# PWM_CON_Outputs.net
KiCad netlist of a schematic drawn in Altium Designer
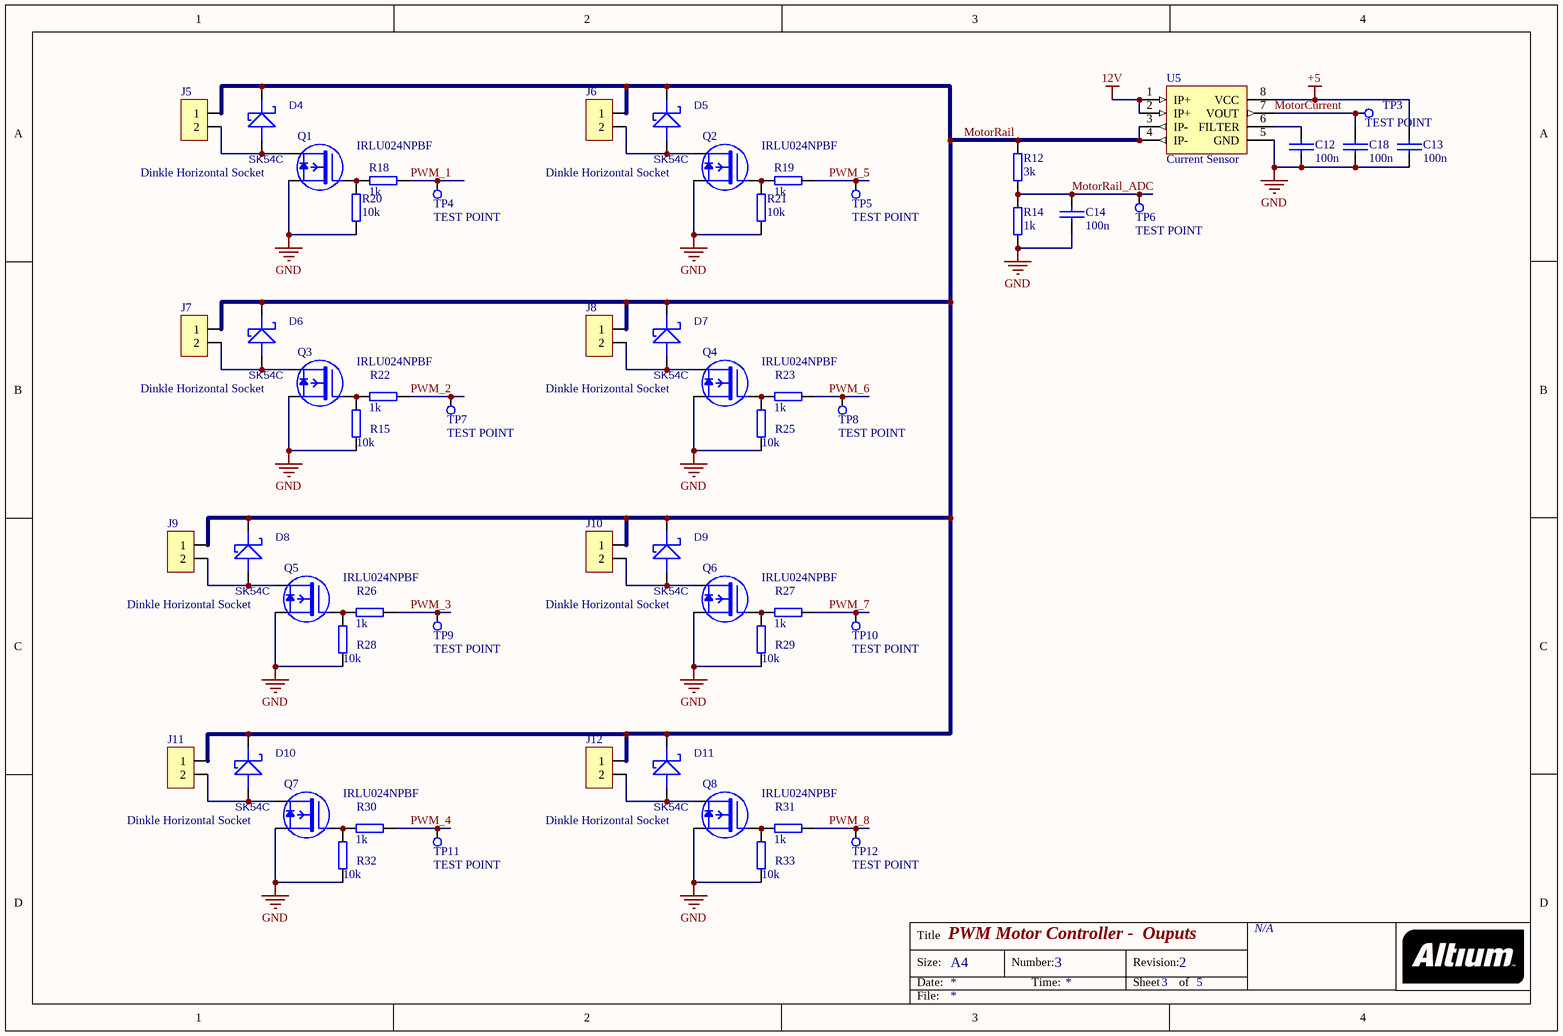
[diagram p0: PWM_CON_Outputs.SchDoc]

(export (version "E")
  (design (tool "Eeschema 10.0.6"))
  (components
    (comp (ref "C12")
      (value "100n")
      (footprint "0603")
      (fields (field (name "PARTNO") "R8835"))
      (libsource (lib "*") (part "CAP"))
    )
    (comp (ref "C13")
      (value "100n")
      (footprint "0603")
      (fields (field (name "PARTNO") "R8835"))
      (libsource (lib "*") (part "CAP"))
    )
    (comp (ref "C14")
      (value "100n")
      (footprint "0603")
      (fields (field (name "PARTNO") "R8835"))
      (libsource (lib "*") (part "CAP"))
    )
    (comp (ref "C18")
      (value "100n")
      (footprint "0603")
      (fields (field (name "PARTNO") "R8835"))
      (libsource (lib "*") (part "CAP"))
    )
    (comp (ref "D4")
      (value "SK54C")
      (footprint "SMC")
      (fields (field (name "PARTNO") "1299291"))
      (libsource (lib "DEVICE") (part "DIODE SCHOTTKY"))
    )
    (comp (ref "D5")
      (value "SK54C")
      (footprint "SMC")
      (fields (field (name "PARTNO") "1299291"))
      (libsource (lib "DEVICE") (part "DIODE SCHOTTKY"))
    )
    (comp (ref "D6")
      (value "SK54C")
      (footprint "SMC")
      (fields (field (name "PARTNO") "1299291"))
      (libsource (lib "DEVICE") (part "DIODE SCHOTTKY"))
    )
    (comp (ref "D7")
      (value "SK54C")
      (footprint "SMC")
      (fields (field (name "PARTNO") "1299291"))
      (libsource (lib "DEVICE") (part "DIODE SCHOTTKY"))
    )
    (comp (ref "D8")
      (value "SK54C")
      (footprint "SMC")
      (fields (field (name "PARTNO") "1299291"))
      (libsource (lib "DEVICE") (part "DIODE SCHOTTKY"))
    )
    (comp (ref "D9")
      (value "SK54C")
      (footprint "SMC")
      (fields (field (name "PARTNO") "1299291"))
      (libsource (lib "DEVICE") (part "DIODE SCHOTTKY"))
    )
    (comp (ref "D10")
      (value "SK54C")
      (footprint "SMC")
      (fields (field (name "PARTNO") "1299291"))
      (libsource (lib "DEVICE") (part "DIODE SCHOTTKY"))
    )
    (comp (ref "D11")
      (value "SK54C")
      (footprint "SMC")
      (fields (field (name "PARTNO") "1299291"))
      (libsource (lib "DEVICE") (part "DIODE SCHOTTKY"))
    )
    (comp (ref "J5")
      (value "Dinkle Horizontal Socket")
      (footprint "WEID2R")
      (fields (field (name "PARTNO") "P2552"))
      (libsource (lib "DEVICE") (part "CON2"))
    )
    (comp (ref "J6")
      (value "Dinkle Horizontal Socket")
      (footprint "WEID2R")
      (fields (field (name "PARTNO") "P2552"))
      (libsource (lib "DEVICE") (part "CON2"))
    )
    (comp (ref "J7")
      (value "Dinkle Horizontal Socket")
      (footprint "WEID2R")
      (fields (field (name "PARTNO") "P2552"))
      (libsource (lib "DEVICE") (part "CON2"))
    )
    (comp (ref "J8")
      (value "Dinkle Horizontal Socket")
      (footprint "WEID2R")
      (fields (field (name "PARTNO") "P2552"))
      (libsource (lib "DEVICE") (part "CON2"))
    )
    (comp (ref "J9")
      (value "Dinkle Horizontal Socket")
      (footprint "WEID2R")
      (fields (field (name "PARTNO") "P2552"))
      (libsource (lib "DEVICE") (part "CON2"))
    )
    (comp (ref "J10")
      (value "Dinkle Horizontal Socket")
      (footprint "WEID2R")
      (fields (field (name "PARTNO") "P2552"))
      (libsource (lib "DEVICE") (part "CON2"))
    )
    (comp (ref "J11")
      (value "Dinkle Horizontal Socket")
      (footprint "WEID2R")
      (fields (field (name "PARTNO") "P2552"))
      (libsource (lib "DEVICE") (part "CON2"))
    )
    (comp (ref "J12")
      (value "Dinkle Horizontal Socket")
      (footprint "WEID2R")
      (fields (field (name "PARTNO") "P2552"))
      (libsource (lib "DEVICE") (part "CON2"))
    )
    (comp (ref "Q1")
      (value "IRLU024NPBF")
      (footprint "TO-251")
      (description "N Channel MOSFET")
      (fields (field (name "PARTNO") "8651329"))
      (libsource (lib "DEVICE") (part "MOSFET-N1DSML"))
    )
    (comp (ref "Q2")
      (value "IRLU024NPBF")
      (footprint "TO-251")
      (description "N Channel MOSFET")
      (fields (field (name "PARTNO") "8651329"))
      (libsource (lib "DEVICE") (part "MOSFET-N1DSML"))
    )
    (comp (ref "Q3")
      (value "IRLU024NPBF")
      (footprint "TO-251")
      (description "N Channel MOSFET")
      (fields (field (name "PARTNO") "8651329"))
      (libsource (lib "DEVICE") (part "MOSFET-N1DSML"))
    )
    (comp (ref "Q4")
      (value "IRLU024NPBF")
      (footprint "TO-251")
      (description "N Channel MOSFET")
      (fields (field (name "PARTNO") "8651329"))
      (libsource (lib "DEVICE") (part "MOSFET-N1DSML"))
    )
    (comp (ref "Q5")
      (value "IRLU024NPBF")
      (footprint "TO-251")
      (description "N Channel MOSFET")
      (fields (field (name "PARTNO") "8651329"))
      (libsource (lib "DEVICE") (part "MOSFET-N1DSML"))
    )
    (comp (ref "Q6")
      (value "IRLU024NPBF")
      (footprint "TO-251")
      (description "N Channel MOSFET")
      (fields (field (name "PARTNO") "8651329"))
      (libsource (lib "DEVICE") (part "MOSFET-N1DSML"))
    )
    (comp (ref "Q7")
      (value "IRLU024NPBF")
      (footprint "TO-251")
      (description "N Channel MOSFET")
      (fields (field (name "PARTNO") "8651329"))
      (libsource (lib "DEVICE") (part "MOSFET-N1DSML"))
    )
    (comp (ref "Q8")
      (value "IRLU024NPBF")
      (footprint "TO-251")
      (description "N Channel MOSFET")
      (fields (field (name "PARTNO") "8651329"))
      (libsource (lib "DEVICE") (part "MOSFET-N1DSML"))
    )
    (comp (ref "R12")
      (value "3k")
      (footprint "0603")
      (description "1% Resistor")
      (fields (field (name "PARTNO") "R1629"))
      (libsource (lib "DEVICE") (part "RES8"))
    )
    (comp (ref "R14")
      (value "1k")
      (footprint "0603")
      (description "1% Resistor")
      (fields (field (name "PARTNO") "R1596"))
      (libsource (lib "") (part "RES8_1"))
    )
    (comp (ref "R15")
      (value "10k")
      (footprint "0603")
      (description "1% Resistor")
      (fields (field (name "PARTNO") "R1668"))
      (libsource (lib "DEVICE") (part "RES8"))
    )
    (comp (ref "R18")
      (value "1k")
      (footprint "0603")
      (description "1% Resistor")
      (fields (field (name "PARTNO") "R1596"))
      (libsource (lib "DEVICE") (part "RES8"))
    )
    (comp (ref "R19")
      (value "1k")
      (footprint "0603")
      (description "1% Resistor")
      (fields (field (name "PARTNO") "R1596"))
      (libsource (lib "DEVICE") (part "RES8"))
    )
    (comp (ref "R20")
      (value "10k")
      (footprint "0603")
      (description "1% Resistor")
      (fields (field (name "PARTNO") "R1668"))
      (libsource (lib "DEVICE") (part "RES8"))
    )
    (comp (ref "R21")
      (value "10k")
      (footprint "0603")
      (description "1% Resistor")
      (fields (field (name "PARTNO") "R1668"))
      (libsource (lib "DEVICE") (part "RES8"))
    )
    (comp (ref "R22")
      (value "1k")
      (footprint "0603")
      (description "1% Resistor")
      (fields (field (name "PARTNO") "R1596"))
      (libsource (lib "DEVICE") (part "RES8"))
    )
    (comp (ref "R23")
      (value "1k")
      (footprint "0603")
      (description "1% Resistor")
      (fields (field (name "PARTNO") "R1596"))
      (libsource (lib "DEVICE") (part "RES8"))
    )
    (comp (ref "R25")
      (value "10k")
      (footprint "0603")
      (description "1% Resistor")
      (fields (field (name "PARTNO") "R1668"))
      (libsource (lib "DEVICE") (part "RES8"))
    )
    (comp (ref "R26")
      (value "1k")
      (footprint "0603")
      (description "1% Resistor")
      (fields (field (name "PARTNO") "R1596"))
      (libsource (lib "DEVICE") (part "RES8"))
    )
    (comp (ref "R27")
      (value "1k")
      (footprint "0603")
      (description "1% Resistor")
      (fields (field (name "PARTNO") "R1596"))
      (libsource (lib "DEVICE") (part "RES8"))
    )
    (comp (ref "R28")
      (value "10k")
      (footprint "0603")
      (description "1% Resistor")
      (fields (field (name "PARTNO") "R1668"))
      (libsource (lib "DEVICE") (part "RES8"))
    )
    (comp (ref "R29")
      (value "10k")
      (footprint "0603")
      (description "1% Resistor")
      (fields (field (name "PARTNO") "R1668"))
      (libsource (lib "DEVICE") (part "RES8"))
    )
    (comp (ref "R30")
      (value "1k")
      (footprint "0603")
      (description "1% Resistor")
      (fields (field (name "PARTNO") "R1596"))
      (libsource (lib "DEVICE") (part "RES8"))
    )
    (comp (ref "R31")
      (value "1k")
      (footprint "0603")
      (description "1% Resistor")
      (fields (field (name "PARTNO") "R1596"))
      (libsource (lib "DEVICE") (part "RES8"))
    )
    (comp (ref "R32")
      (value "10k")
      (footprint "0603")
      (description "1% Resistor")
      (fields (field (name "PARTNO") "R1668"))
      (libsource (lib "DEVICE") (part "RES8"))
    )
    (comp (ref "R33")
      (value "10k")
      (footprint "0603")
      (description "1% Resistor")
      (fields (field (name "PARTNO") "R1668"))
      (libsource (lib "DEVICE") (part "RES8"))
    )
    (comp (ref "TP3")
      (value "TEST POINT")
      (footprint "TEST POINT")
      (description "Probe compatible test point")
      (libsource (lib "DEVICE") (part "TEST POINT"))
    )
    (comp (ref "TP4")
      (value "TEST POINT")
      (footprint "TEST POINT")
      (description "Probe compatible test point")
      (libsource (lib "DEVICE") (part "TEST POINT"))
    )
    (comp (ref "TP5")
      (value "TEST POINT")
      (footprint "TEST POINT")
      (description "Probe compatible test point")
      (libsource (lib "DEVICE") (part "TEST POINT"))
    )
    (comp (ref "TP6")
      (value "TEST POINT")
      (footprint "TEST POINT")
      (description "Probe compatible test point")
      (libsource (lib "DEVICE") (part "TEST POINT"))
    )
    (comp (ref "TP7")
      (value "TEST POINT")
      (footprint "TEST POINT")
      (description "Probe compatible test point")
      (libsource (lib "DEVICE") (part "TEST POINT"))
    )
    (comp (ref "TP8")
      (value "TEST POINT")
      (footprint "TEST POINT")
      (description "Probe compatible test point")
      (libsource (lib "DEVICE") (part "TEST POINT"))
    )
    (comp (ref "TP9")
      (value "TEST POINT")
      (footprint "TEST POINT")
      (description "Probe compatible test point")
      (libsource (lib "DEVICE") (part "TEST POINT"))
    )
    (comp (ref "TP10")
      (value "TEST POINT")
      (footprint "TEST POINT")
      (description "Probe compatible test point")
      (libsource (lib "DEVICE") (part "TEST POINT"))
    )
    (comp (ref "TP11")
      (value "TEST POINT")
      (footprint "TEST POINT")
      (description "Probe compatible test point")
      (libsource (lib "DEVICE") (part "TEST POINT"))
    )
    (comp (ref "TP12")
      (value "TEST POINT")
      (footprint "TEST POINT")
      (description "Probe compatible test point")
      (libsource (lib "DEVICE") (part "TEST POINT"))
    )
    (comp (ref "U5")
      (value "Current Sensor")
      (footprint "so-8")
      (description "+/- XA Current Sensor")
      (libsource (lib "TomsSchLib") (part "ACS714"))
    )
  )
  (nets
    (net (code "1") (name "+5") (class "Default")
      (node (ref "C13") (pin "2") (pintype "passive"))
      (node (ref "U5") (pin "8") (pinfunction "VCC_8") (pintype "power_in"))
    )
    (net (code "2") (name "/MotorCurrent") (class "Default")
      (node (ref "C18") (pin "2") (pintype "passive"))
      (node (ref "TP3") (pin "1") (pinfunction "1_1") (pintype "passive"))
      (node (ref "U5") (pin "7") (pinfunction "VOUT_7") (pintype "output"))
    )
    (net (code "3") (name "/MotorRail") (class "Default")
      (node (ref "D10") (pin "K") (pinfunction "K_K") (pintype "passive"))
      (node (ref "D11") (pin "K") (pinfunction "K_K") (pintype "passive"))
      (node (ref "D4") (pin "K") (pinfunction "K_K") (pintype "passive"))
      (node (ref "D5") (pin "K") (pinfunction "K_K") (pintype "passive"))
      (node (ref "D6") (pin "K") (pinfunction "K_K") (pintype "passive"))
      (node (ref "D7") (pin "K") (pinfunction "K_K") (pintype "passive"))
      (node (ref "D8") (pin "K") (pinfunction "K_K") (pintype "passive"))
      (node (ref "D9") (pin "K") (pinfunction "K_K") (pintype "passive"))
      (node (ref "J10") (pin "1") (pinfunction "1_1") (pintype "passive"))
      (node (ref "J11") (pin "1") (pinfunction "1_1") (pintype "passive"))
      (node (ref "J12") (pin "1") (pinfunction "1_1") (pintype "passive"))
      (node (ref "J5") (pin "1") (pinfunction "1_1") (pintype "passive"))
      (node (ref "J6") (pin "1") (pinfunction "1_1") (pintype "passive"))
      (node (ref "J7") (pin "1") (pinfunction "1_1") (pintype "passive"))
      (node (ref "J8") (pin "1") (pinfunction "1_1") (pintype "passive"))
      (node (ref "J9") (pin "1") (pinfunction "1_1") (pintype "passive"))
      (node (ref "R12") (pin "2") (pintype "passive"))
      (node (ref "U5") (pin "3") (pinfunction "IP-_3") (pintype "output"))
      (node (ref "U5") (pin "4") (pinfunction "IP-_4") (pintype "output"))
    )
    (net (code "4") (name "/MotorRail_ADC") (class "Default")
      (node (ref "C14") (pin "2") (pintype "passive"))
      (node (ref "R12") (pin "1") (pintype "passive"))
      (node (ref "R14") (pin "1") (pintype "passive"))
      (node (ref "TP6") (pin "1") (pinfunction "1_1") (pintype "passive"))
    )
    (net (code "5") (name "/PWM_1") (class "Default")
      (node (ref "R18") (pin "1") (pintype "passive"))
      (node (ref "TP4") (pin "1") (pinfunction "1_1") (pintype "passive"))
    )
    (net (code "6") (name "/PWM_2") (class "Default")
      (node (ref "R22") (pin "1") (pintype "passive"))
      (node (ref "TP7") (pin "1") (pinfunction "1_1") (pintype "passive"))
    )
    (net (code "7") (name "/PWM_3") (class "Default")
      (node (ref "R26") (pin "1") (pintype "passive"))
      (node (ref "TP9") (pin "1") (pinfunction "1_1") (pintype "passive"))
    )
    (net (code "8") (name "/PWM_4") (class "Default")
      (node (ref "R30") (pin "1") (pintype "passive"))
      (node (ref "TP11") (pin "1") (pinfunction "1_1") (pintype "passive"))
    )
    (net (code "9") (name "/PWM_5") (class "Default")
      (node (ref "R19") (pin "1") (pintype "passive"))
      (node (ref "TP5") (pin "1") (pinfunction "1_1") (pintype "passive"))
    )
    (net (code "10") (name "/PWM_6") (class "Default")
      (node (ref "R23") (pin "1") (pintype "passive"))
      (node (ref "TP8") (pin "1") (pinfunction "1_1") (pintype "passive"))
    )
    (net (code "11") (name "/PWM_7") (class "Default")
      (node (ref "R27") (pin "1") (pintype "passive"))
      (node (ref "TP10") (pin "1") (pinfunction "1_1") (pintype "passive"))
    )
    (net (code "12") (name "/PWM_8") (class "Default")
      (node (ref "R31") (pin "1") (pintype "passive"))
      (node (ref "TP12") (pin "1") (pinfunction "1_1") (pintype "passive"))
    )
    (net (code "13") (name "12V") (class "Default")
      (node (ref "U5") (pin "1") (pinfunction "IP+_1") (pintype "input"))
      (node (ref "U5") (pin "2") (pinfunction "IP+_2") (pintype "input"))
    )
    (net (code "14") (name "GND") (class "Default")
      (node (ref "C12") (pin "1") (pintype "passive"))
      (node (ref "C13") (pin "1") (pintype "passive"))
      (node (ref "C14") (pin "1") (pintype "passive"))
      (node (ref "C18") (pin "1") (pintype "passive"))
      (node (ref "Q1") (pin "S") (pinfunction "S_S") (pintype "passive"))
      (node (ref "Q2") (pin "S") (pinfunction "S_S") (pintype "passive"))
      (node (ref "Q3") (pin "S") (pinfunction "S_S") (pintype "passive"))
      (node (ref "Q4") (pin "S") (pinfunction "S_S") (pintype "passive"))
      (node (ref "Q5") (pin "S") (pinfunction "S_S") (pintype "passive"))
      (node (ref "Q6") (pin "S") (pinfunction "S_S") (pintype "passive"))
      (node (ref "Q7") (pin "S") (pinfunction "S_S") (pintype "passive"))
      (node (ref "Q8") (pin "S") (pinfunction "S_S") (pintype "passive"))
      (node (ref "R14") (pin "2") (pintype "passive"))
      (node (ref "R15") (pin "1") (pintype "passive"))
      (node (ref "R20") (pin "1") (pintype "passive"))
      (node (ref "R21") (pin "1") (pintype "passive"))
      (node (ref "R25") (pin "1") (pintype "passive"))
      (node (ref "R28") (pin "1") (pintype "passive"))
      (node (ref "R29") (pin "1") (pintype "passive"))
      (node (ref "R32") (pin "1") (pintype "passive"))
      (node (ref "R33") (pin "1") (pintype "passive"))
      (node (ref "U5") (pin "5") (pinfunction "GND_5") (pintype "power_in"))
    )
    (net (code "15") (name "Net-(D4-PadA)") (class "Default")
      (node (ref "D4") (pin "A") (pinfunction "A_A") (pintype "passive"))
      (node (ref "J5") (pin "2") (pinfunction "2_2") (pintype "passive"))
      (node (ref "Q1") (pin "D") (pinfunction "D_D") (pintype "passive"))
    )
    (net (code "16") (name "Net-(D5-PadA)") (class "Default")
      (node (ref "D5") (pin "A") (pinfunction "A_A") (pintype "passive"))
      (node (ref "J6") (pin "2") (pinfunction "2_2") (pintype "passive"))
      (node (ref "Q2") (pin "D") (pinfunction "D_D") (pintype "passive"))
    )
    (net (code "17") (name "Net-(D6-PadA)") (class "Default")
      (node (ref "D6") (pin "A") (pinfunction "A_A") (pintype "passive"))
      (node (ref "J7") (pin "2") (pinfunction "2_2") (pintype "passive"))
      (node (ref "Q3") (pin "D") (pinfunction "D_D") (pintype "passive"))
    )
    (net (code "18") (name "Net-(D7-PadA)") (class "Default")
      (node (ref "D7") (pin "A") (pinfunction "A_A") (pintype "passive"))
      (node (ref "J8") (pin "2") (pinfunction "2_2") (pintype "passive"))
      (node (ref "Q4") (pin "D") (pinfunction "D_D") (pintype "passive"))
    )
    (net (code "19") (name "Net-(D8-PadA)") (class "Default")
      (node (ref "D8") (pin "A") (pinfunction "A_A") (pintype "passive"))
      (node (ref "J9") (pin "2") (pinfunction "2_2") (pintype "passive"))
      (node (ref "Q5") (pin "D") (pinfunction "D_D") (pintype "passive"))
    )
    (net (code "20") (name "Net-(D9-PadA)") (class "Default")
      (node (ref "D9") (pin "A") (pinfunction "A_A") (pintype "passive"))
      (node (ref "J10") (pin "2") (pinfunction "2_2") (pintype "passive"))
      (node (ref "Q6") (pin "D") (pinfunction "D_D") (pintype "passive"))
    )
    (net (code "21") (name "Net-(D10-PadA)") (class "Default")
      (node (ref "D10") (pin "A") (pinfunction "A_A") (pintype "passive"))
      (node (ref "J11") (pin "2") (pinfunction "2_2") (pintype "passive"))
      (node (ref "Q7") (pin "D") (pinfunction "D_D") (pintype "passive"))
    )
    (net (code "22") (name "Net-(D11-PadA)") (class "Default")
      (node (ref "D11") (pin "A") (pinfunction "A_A") (pintype "passive"))
      (node (ref "J12") (pin "2") (pinfunction "2_2") (pintype "passive"))
      (node (ref "Q8") (pin "D") (pinfunction "D_D") (pintype "passive"))
    )
    (net (code "23") (name "Net-(Q1-PadG)") (class "Default")
      (node (ref "Q1") (pin "G") (pinfunction "G_G") (pintype "passive"))
      (node (ref "R18") (pin "2") (pintype "passive"))
      (node (ref "R20") (pin "2") (pintype "passive"))
    )
    (net (code "24") (name "Net-(Q2-PadG)") (class "Default")
      (node (ref "Q2") (pin "G") (pinfunction "G_G") (pintype "passive"))
      (node (ref "R19") (pin "2") (pintype "passive"))
      (node (ref "R21") (pin "2") (pintype "passive"))
    )
    (net (code "25") (name "Net-(Q3-PadG)") (class "Default")
      (node (ref "Q3") (pin "G") (pinfunction "G_G") (pintype "passive"))
      (node (ref "R15") (pin "2") (pintype "passive"))
      (node (ref "R22") (pin "2") (pintype "passive"))
    )
    (net (code "26") (name "Net-(Q4-PadG)") (class "Default")
      (node (ref "Q4") (pin "G") (pinfunction "G_G") (pintype "passive"))
      (node (ref "R23") (pin "2") (pintype "passive"))
      (node (ref "R25") (pin "2") (pintype "passive"))
    )
    (net (code "27") (name "Net-(Q5-PadG)") (class "Default")
      (node (ref "Q5") (pin "G") (pinfunction "G_G") (pintype "passive"))
      (node (ref "R26") (pin "2") (pintype "passive"))
      (node (ref "R28") (pin "2") (pintype "passive"))
    )
    (net (code "28") (name "Net-(Q6-PadG)") (class "Default")
      (node (ref "Q6") (pin "G") (pinfunction "G_G") (pintype "passive"))
      (node (ref "R27") (pin "2") (pintype "passive"))
      (node (ref "R29") (pin "2") (pintype "passive"))
    )
    (net (code "29") (name "Net-(Q7-PadG)") (class "Default")
      (node (ref "Q7") (pin "G") (pinfunction "G_G") (pintype "passive"))
      (node (ref "R30") (pin "2") (pintype "passive"))
      (node (ref "R32") (pin "2") (pintype "passive"))
    )
    (net (code "30") (name "Net-(Q8-PadG)") (class "Default")
      (node (ref "Q8") (pin "G") (pinfunction "G_G") (pintype "passive"))
      (node (ref "R31") (pin "2") (pintype "passive"))
      (node (ref "R33") (pin "2") (pintype "passive"))
    )
    (net (code "31") (name "Net-(U5-FILTER)") (class "Default")
      (node (ref "C12") (pin "2") (pintype "passive"))
      (node (ref "U5") (pin "6") (pinfunction "FILTER_6") (pintype "passive"))
    )
  )
)
